# version_2.net
KiCad netlist of a schematic drawn in EAGLE
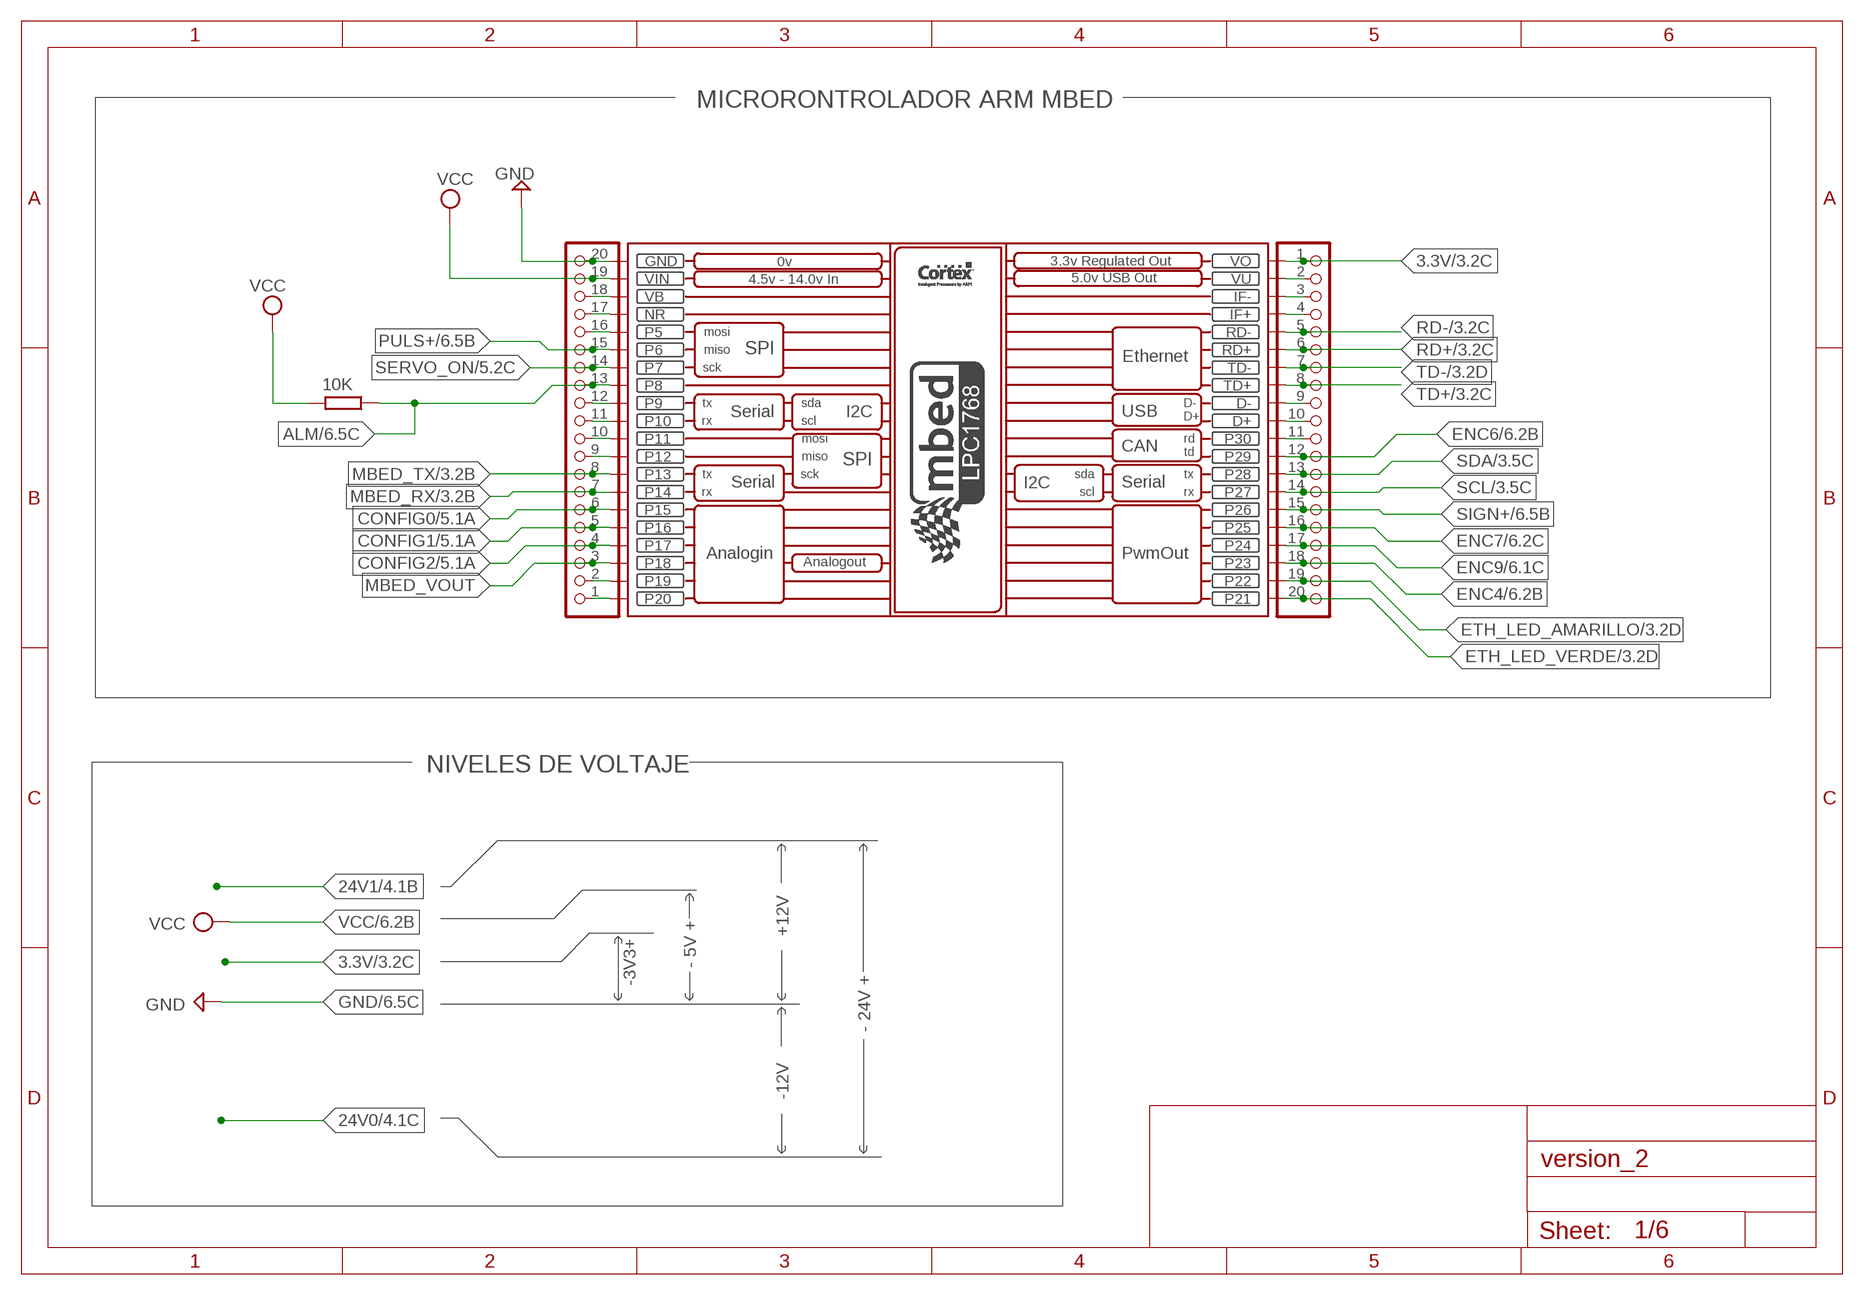
[diagram p0: schematic, sheet 1]
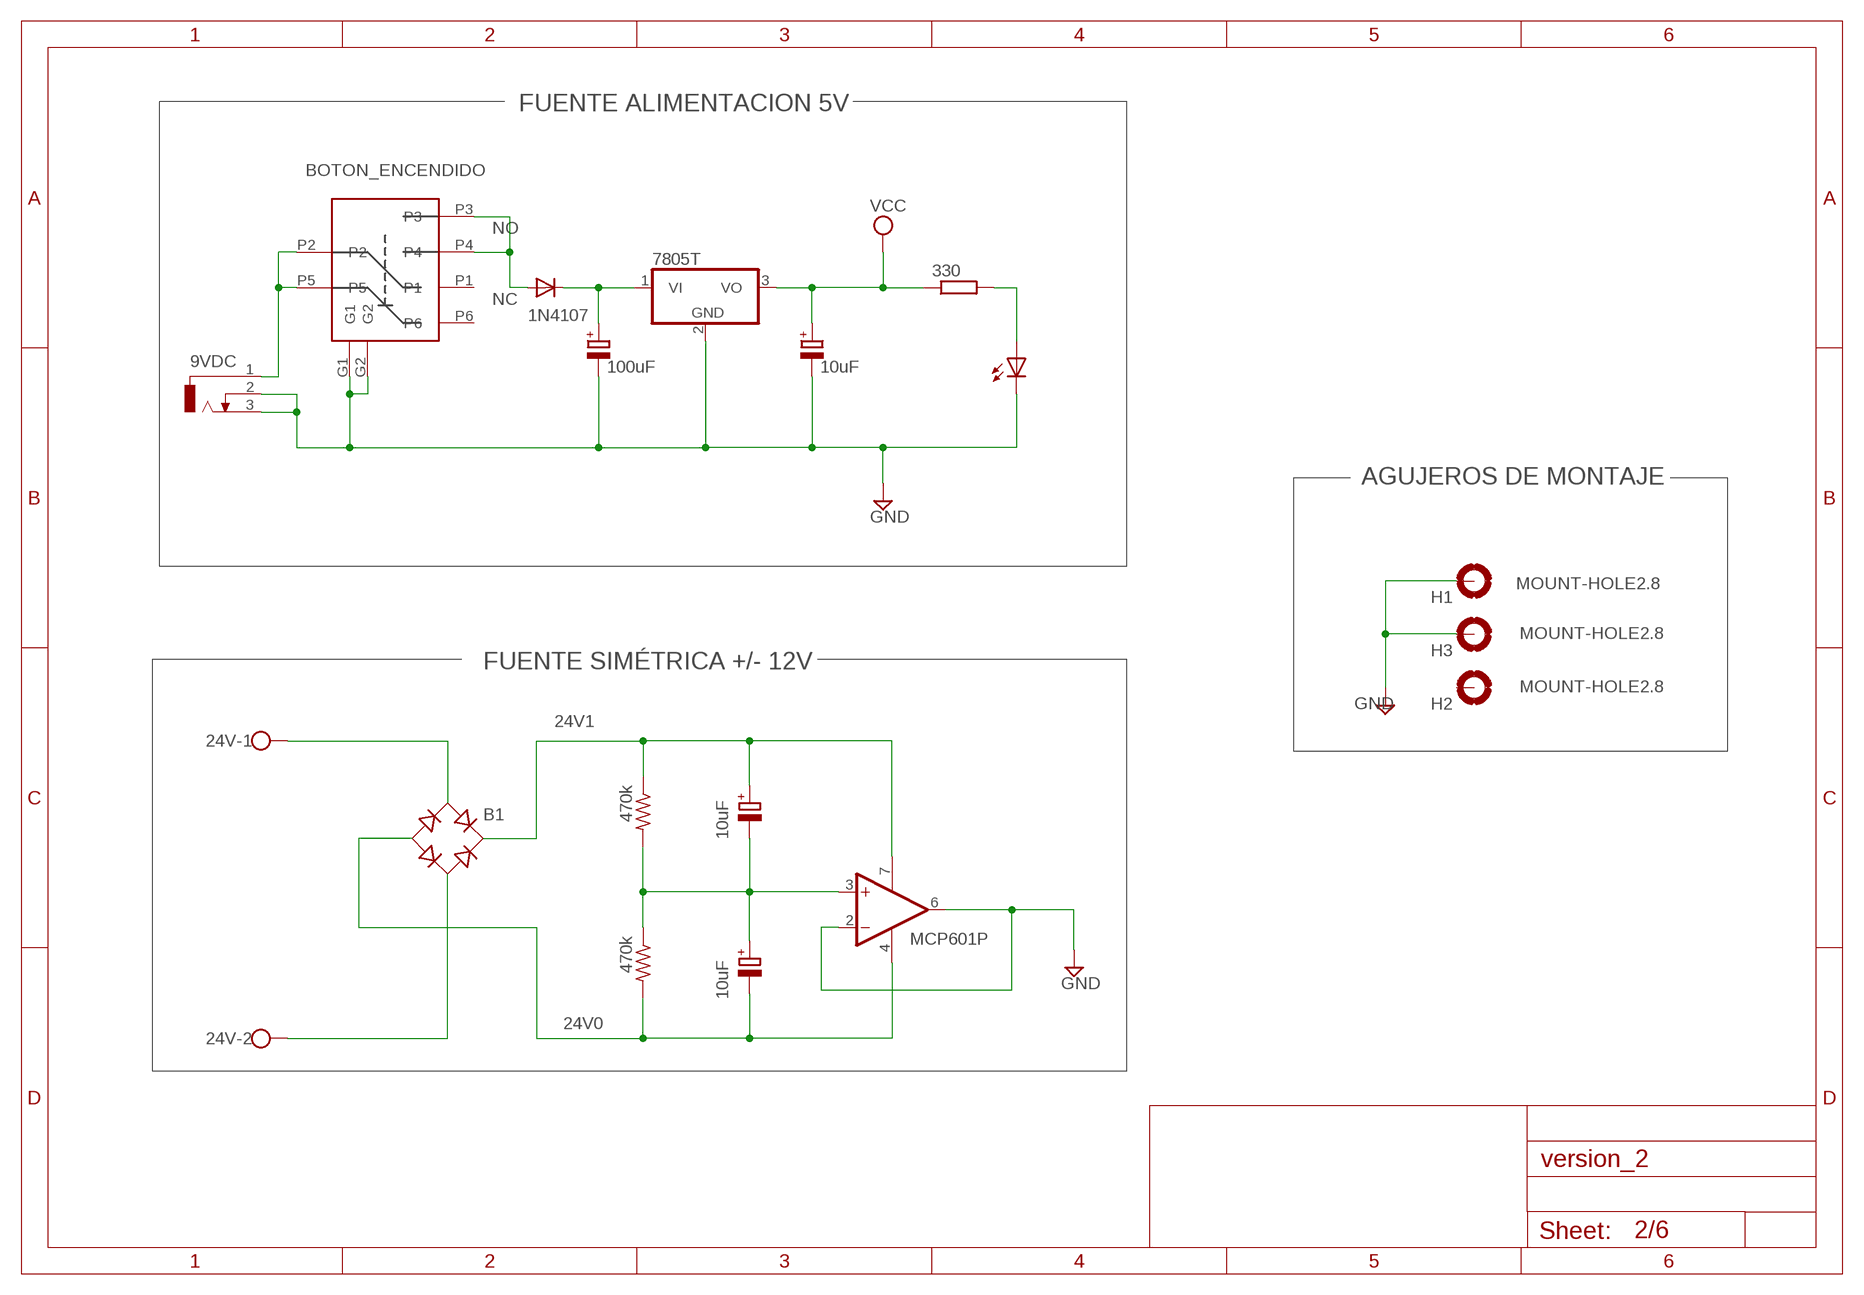
[diagram p1: schematic, sheet 2]
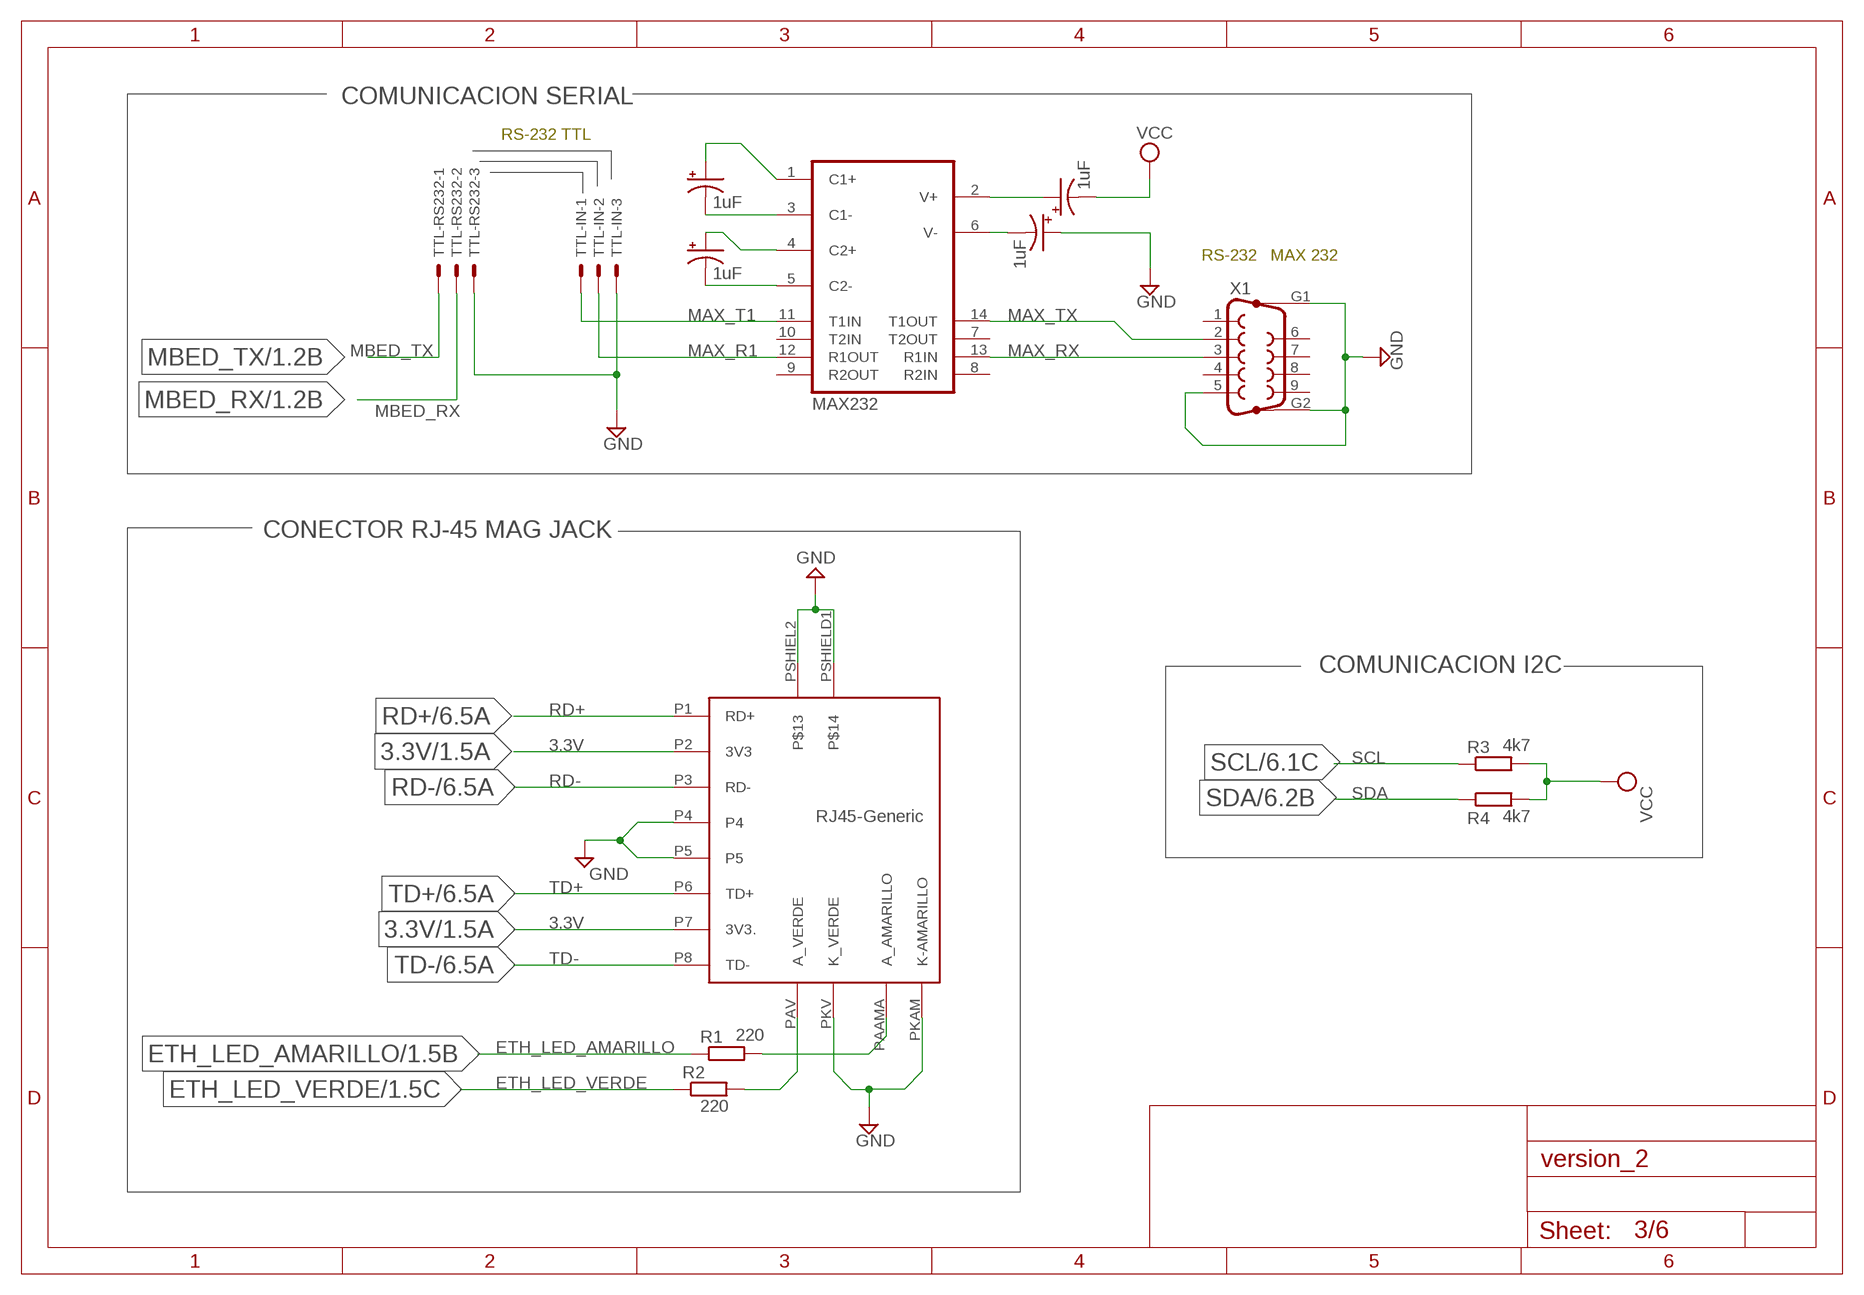
[diagram p2: schematic, sheet 3]
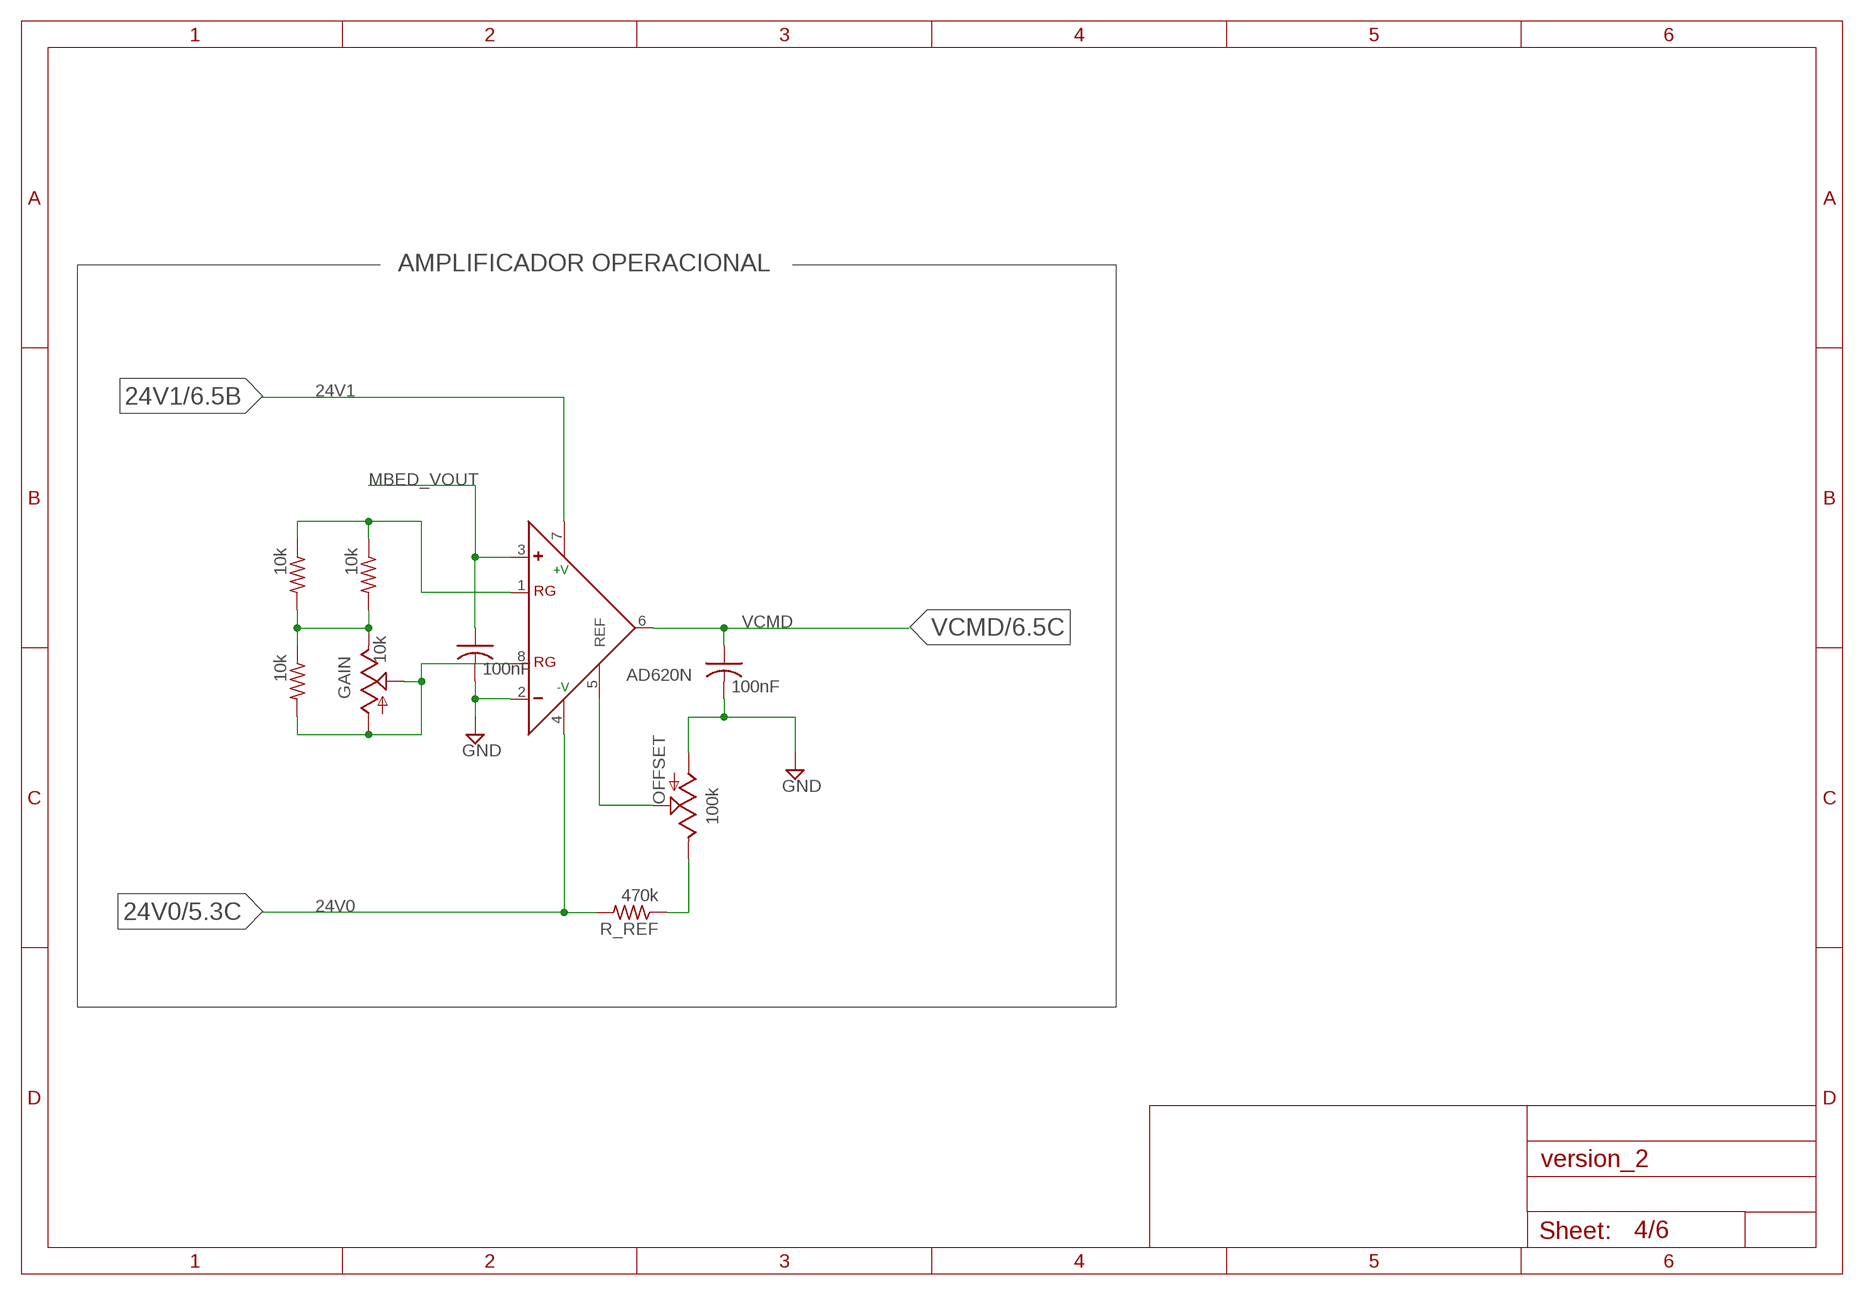
[diagram p3: schematic, sheet 4]
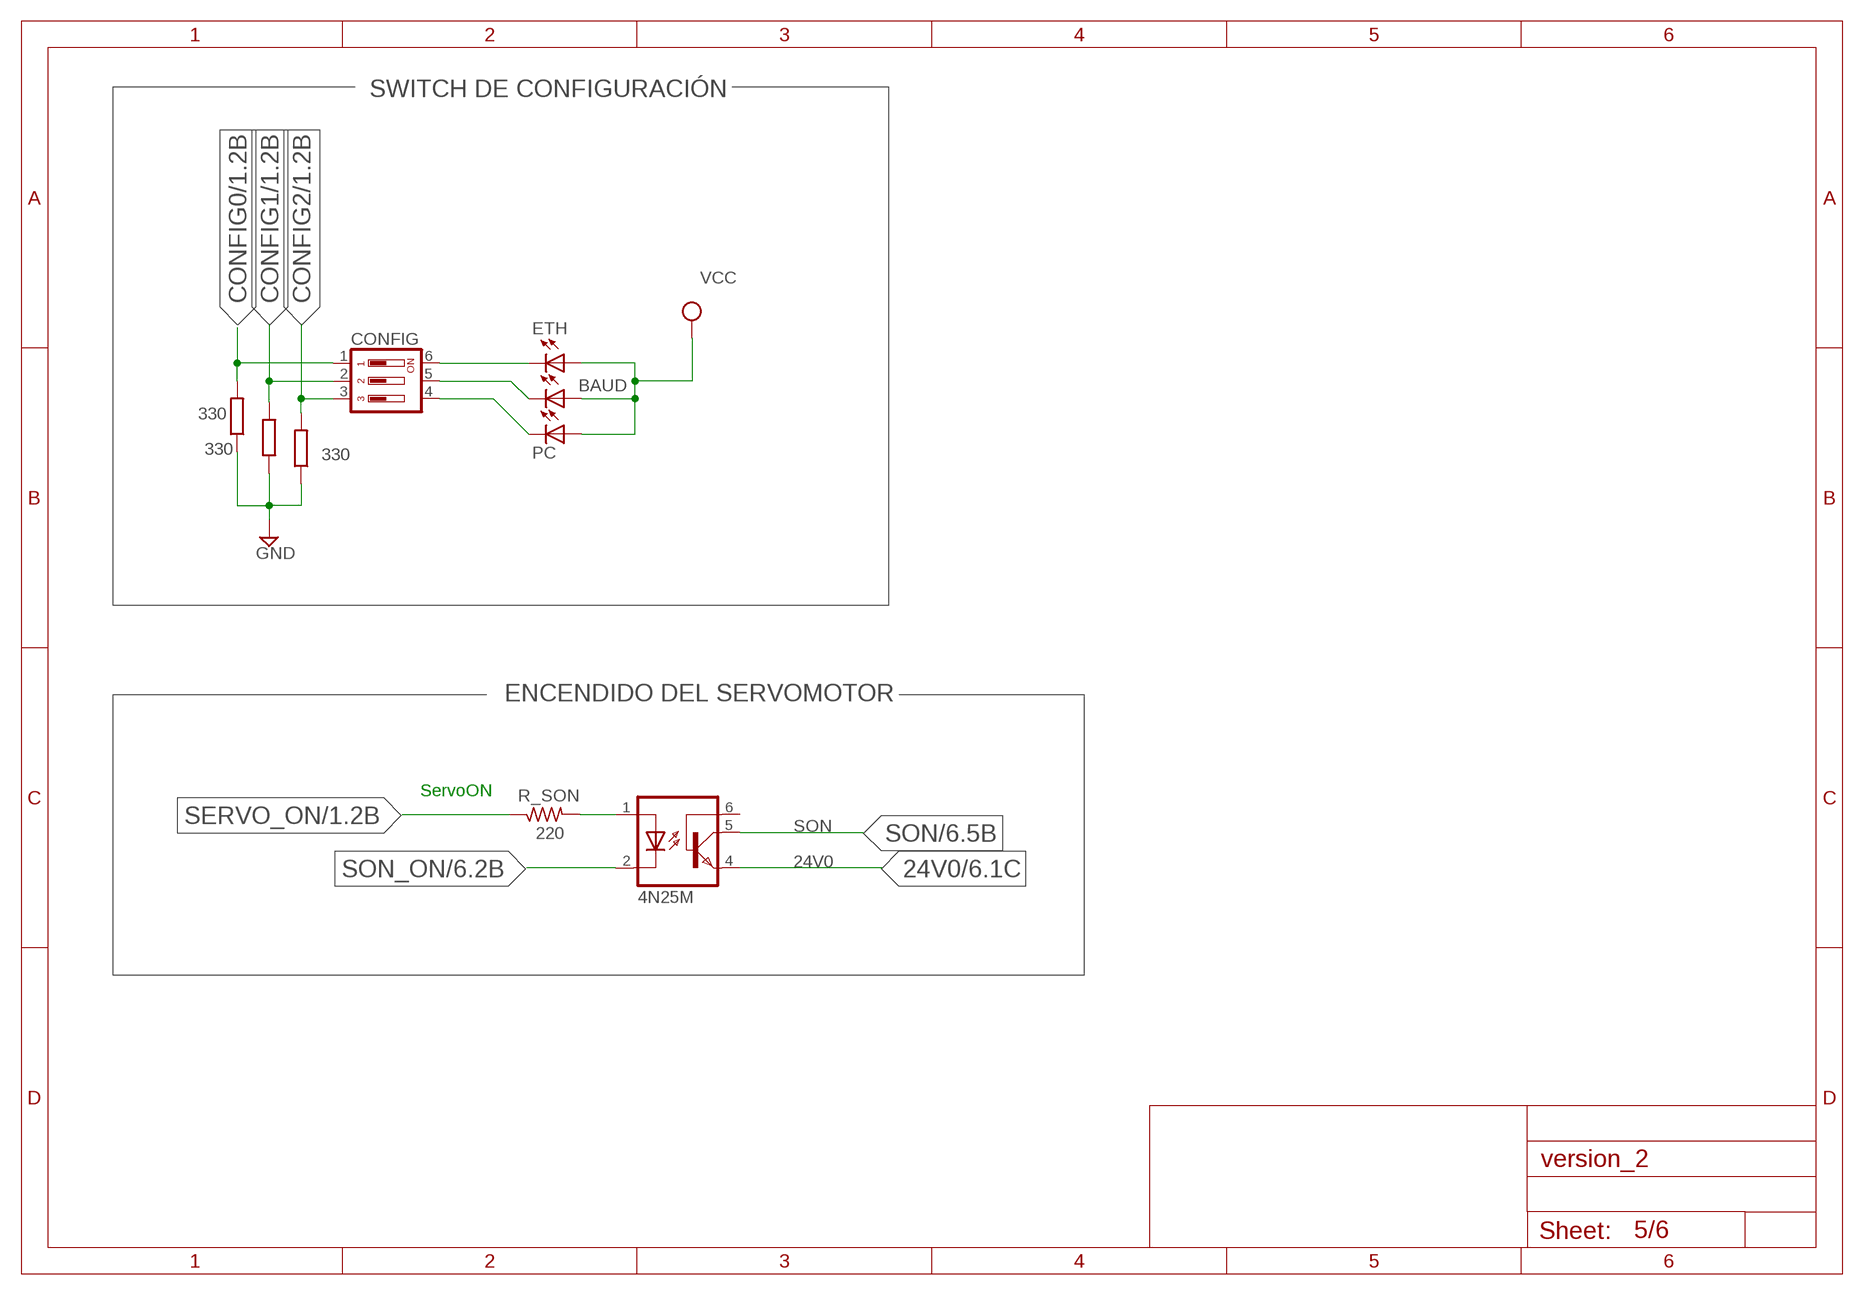
[diagram p4: schematic, sheet 5]
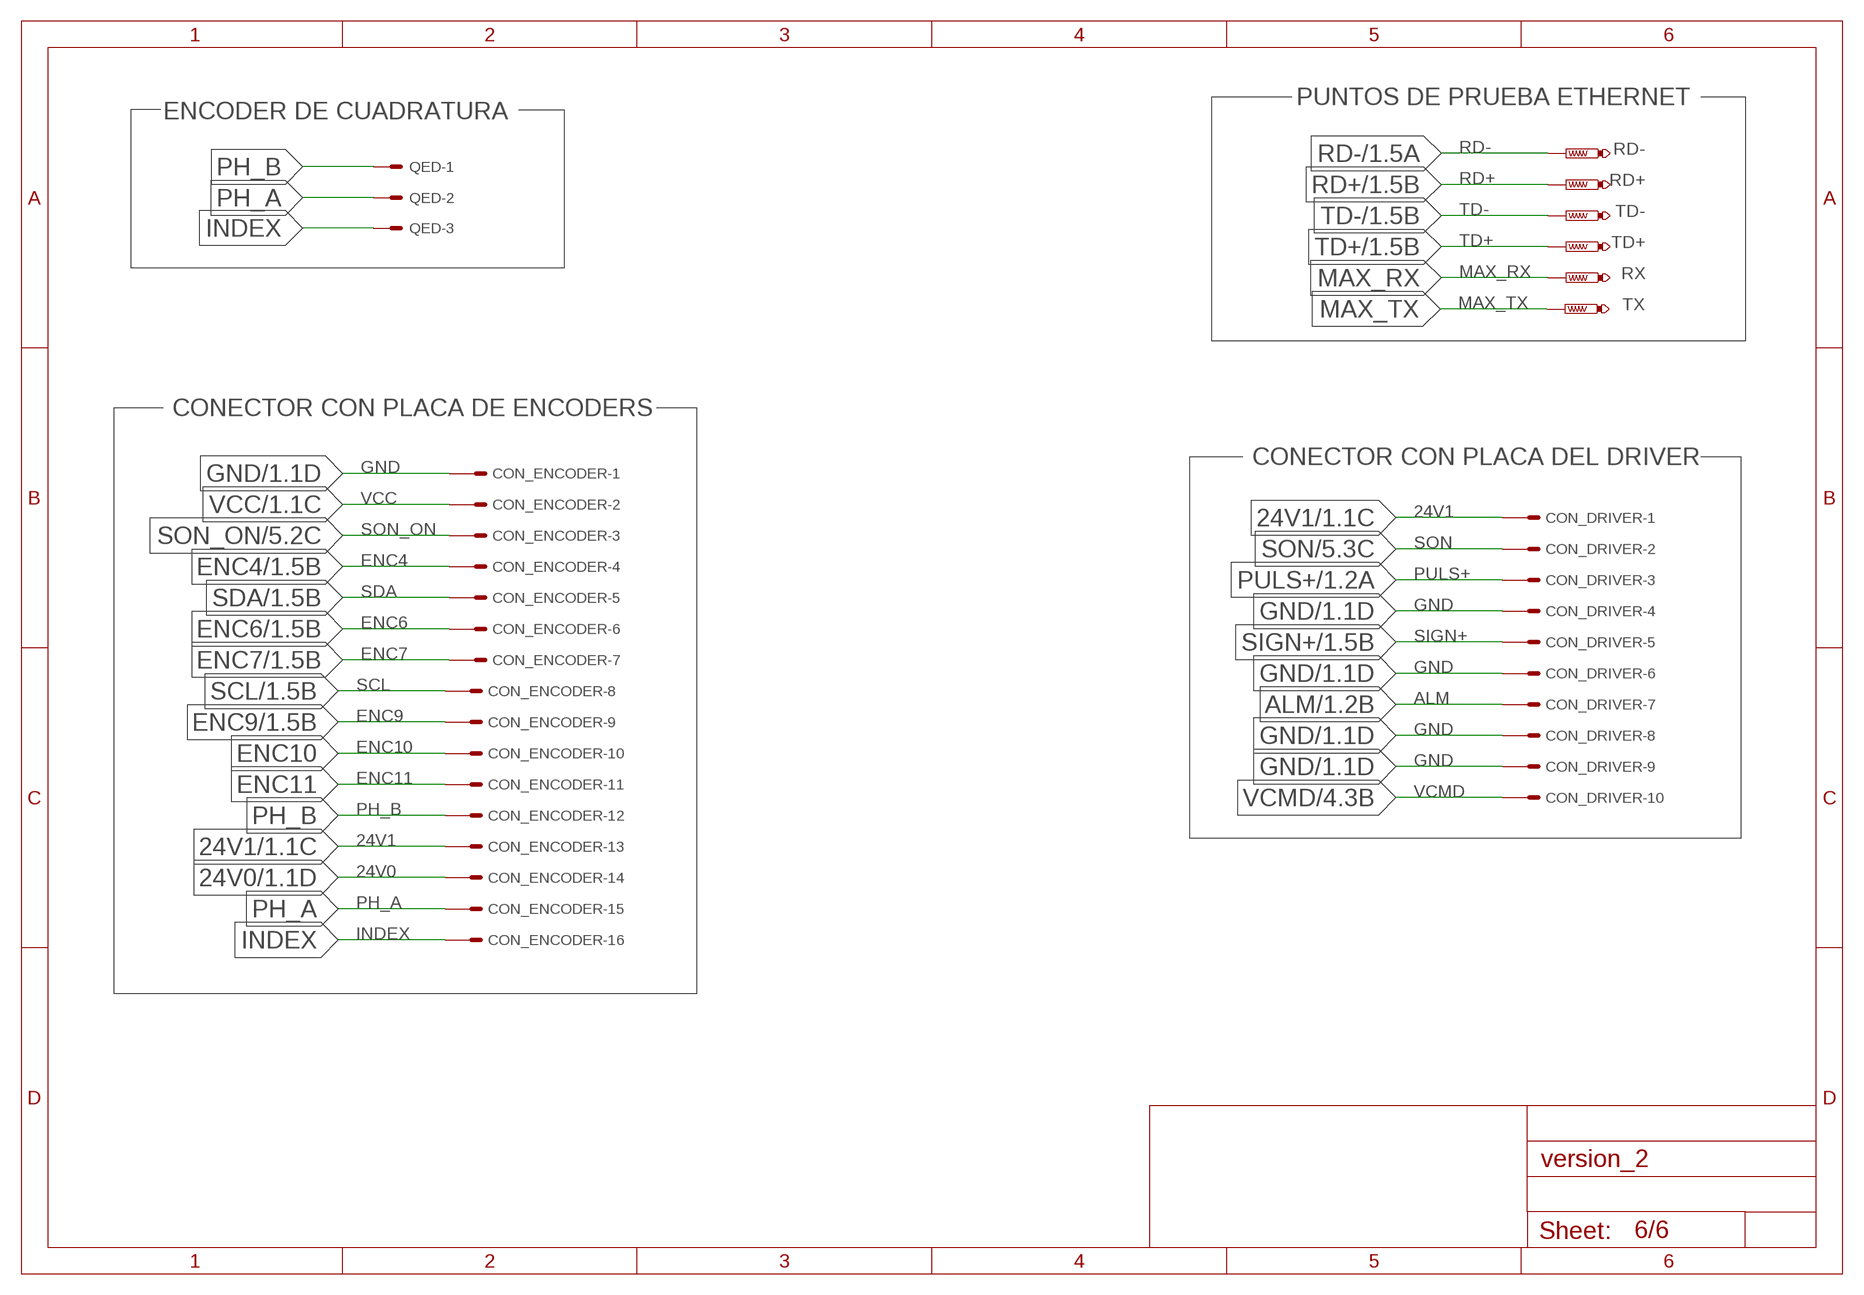
[diagram p5: schematic, sheet 6]

(export (version "E")
  (design (tool "Eeschema 10.0.6"))
  (components
    (comp (ref "CON_DRIVER")
      (value "057-010-1")
      (footprint "eagle-import:057-010-1")
      (libsource (lib "eagle-import") (part "057-010-1"))
    )
    (comp (ref "CON_ENCODER")
      (value "057-016-1")
      (footprint "eagle-import:057-016-1")
      (libsource (lib "eagle-import") (part "057-016-1"))
    )
    (comp (ref "QED")
      (value "22-23-2031")
      (footprint "eagle-import:22-23-2031")
      (fields (field (name "MF") "MOLEX"))
      (libsource (lib "eagle-import") (part "22-23-2031"))
    )
    (comp (ref "RD+")
      (value "PTR1PAD1-13Y")
      (footprint "eagle-import:P1-13Y")
      (libsource (lib "eagle-import") (part "PTR1PAD1-13Y"))
    )
    (comp (ref "RD-")
      (value "PTR1PAD1-13Y")
      (footprint "eagle-import:P1-13Y")
      (libsource (lib "eagle-import") (part "PTR1PAD1-13Y"))
    )
    (comp (ref "RX")
      (value "PTR1PAD1-13Y")
      (footprint "eagle-import:P1-13Y")
      (libsource (lib "eagle-import") (part "PTR1PAD1-13Y"))
    )
    (comp (ref "TD+")
      (value "PTR1PAD1-13Y")
      (footprint "eagle-import:P1-13Y")
      (libsource (lib "eagle-import") (part "PTR1PAD1-13Y"))
    )
    (comp (ref "TD-")
      (value "PTR1PAD1-13Y")
      (footprint "eagle-import:P1-13Y")
      (libsource (lib "eagle-import") (part "PTR1PAD1-13Y"))
    )
    (comp (ref "TX")
      (value "PTR1PAD1-13Y")
      (footprint "eagle-import:P1-13Y")
      (libsource (lib "eagle-import") (part "PTR1PAD1-13Y"))
    )
    (comp (ref "C1_MAX")
      (value "1uF")
      (footprint "eagle-import:E2,5-6E")
      (libsource (lib "eagle-import") (part "CPOL-USE2,5-6E"))
    )
    (comp (ref "C2_MAX")
      (value "1uF")
      (footprint "eagle-import:E2,5-6E")
      (libsource (lib "eagle-import") (part "CPOL-USE2,5-6E"))
    )
    (comp (ref "C3_MAX")
      (value "1uF")
      (footprint "eagle-import:E2,5-6E")
      (libsource (lib "eagle-import") (part "CPOL-USE2,5-6E"))
    )
    (comp (ref "C4_MAX")
      (value "1uF")
      (footprint "eagle-import:E2,5-6E")
      (libsource (lib "eagle-import") (part "CPOL-USE2,5-6E"))
    )
    (comp (ref "IC1")
      (value "MAX232")
      (footprint "eagle-import:DIL16")
      (libsource (lib "eagle-import") (part "MAX232"))
    )
    (comp (ref "R1")
      (value "220")
      (footprint "eagle-import:0207_15")
      (libsource (lib "eagle-import") (part "R-EU_0207/15"))
    )
    (comp (ref "R2")
      (value "220")
      (footprint "eagle-import:0207_15")
      (libsource (lib "eagle-import") (part "R-EU_0207/15"))
    )
    (comp (ref "R3")
      (value "4k7")
      (footprint "eagle-import:0204_7")
      (libsource (lib "eagle-import") (part "R-EU_0204/7"))
    )
    (comp (ref "R4")
      (value "4k7")
      (footprint "eagle-import:0204_7")
      (libsource (lib "eagle-import") (part "R-EU_0204/7"))
    )
    (comp (ref "TTL-IN")
      (value "22-23-2031")
      (footprint "eagle-import:22-23-2031")
      (fields (field (name "MF") "MOLEX"))
      (libsource (lib "eagle-import") (part "22-23-2031"))
    )
    (comp (ref "TTL-RS232")
      (value "22-23-2031")
      (footprint "eagle-import:22-23-2031")
      (fields (field (name "MF") "MOLEX"))
      (libsource (lib "eagle-import") (part "22-23-2031"))
    )
    (comp (ref "U$1")
      (value "RJ-45-GENERIC")
      (footprint "eagle-import:RJ45-GENERIC")
      (libsource (lib "eagle-import") (part "RJ-45-GENERIC"))
    )
    (comp (ref "X1")
      (value "F09HP")
      (footprint "eagle-import:F09HP")
      (libsource (lib "eagle-import") (part "F09HP"))
    )
    (comp (ref "JP_LEFT")
      (value "PINHD-1X20")
      (footprint "eagle-import:1X20")
      (libsource (lib "eagle-import") (part "PINHD-1X20"))
    )
    (comp (ref "JP_RIGHT")
      (value "PINHD-1X20")
      (footprint "eagle-import:1X20")
      (libsource (lib "eagle-import") (part "PINHD-1X20"))
    )
    (comp (ref "KIT1")
      (value "MBED_NXP_LPC1768")
      (footprint "eagle-import:MBED-KIT")
      (libsource (lib "eagle-import") (part "MBED_NXP_LPC1768"))
    )
    (comp (ref "R16_ALM")
      (value "10K")
      (footprint "eagle-import:0207_12")
      (libsource (lib "eagle-import") (part "R-EU_0207/12"))
    )
    (comp (ref "C3_AOUT")
      (value "100nF")
      (footprint "eagle-import:C025-024X044")
      (libsource (lib "eagle-import") (part "C-US025-024X044"))
    )
    (comp (ref "C5_AOUT")
      (value "100nF")
      (footprint "eagle-import:C025-024X044")
      (libsource (lib "eagle-import") (part "C-US025-024X044"))
    )
    (comp (ref "GAIN")
      (value "10k")
      (footprint "eagle-import:RJ9W")
      (libsource (lib "eagle-import") (part "TRIM_US-RJ9W"))
    )
    (comp (ref "IC4")
      (value "AD620N")
      (footprint "eagle-import:DIL08")
      (libsource (lib "eagle-import") (part "AD620N"))
    )
    (comp (ref "OFFSET")
      (value "100k")
      (footprint "eagle-import:RJ9W")
      (libsource (lib "eagle-import") (part "TRIM_US-RJ9W"))
    )
    (comp (ref "R1_G")
      (value "10k")
      (footprint "eagle-import:0204_7")
      (libsource (lib "eagle-import") (part "resistor_R-US_0204/7"))
    )
    (comp (ref "R2_G")
      (value "10k")
      (footprint "eagle-import:0204_7")
      (libsource (lib "eagle-import") (part "resistor_R-US_0204/7"))
    )
    (comp (ref "R3_G")
      (value "10k")
      (footprint "eagle-import:0204_7")
      (libsource (lib "eagle-import") (part "resistor_R-US_0204/7"))
    )
    (comp (ref "R_REF")
      (value "470k")
      (footprint "eagle-import:0204_7")
      (libsource (lib "eagle-import") (part "resistor_R-US_0204/7"))
    )
    (comp (ref "9VDC")
      (value "DCJ0303")
      (footprint "eagle-import:DCJ0303")
      (libsource (lib "eagle-import") (part "DCJ0303"))
    )
    (comp (ref "24V")
      (value "W237-02P")
      (footprint "eagle-import:W237-132")
      (libsource (lib "eagle-import") (part "W237-02P"))
    )
    (comp (ref "B1")
      (value "RB1A")
      (footprint "eagle-import:RB1A")
      (libsource (lib "eagle-import") (part "RB1A"))
    )
    (comp (ref "C1_+24")
      (value "10uF")
      (footprint "eagle-import:TT5D7")
      (libsource (lib "eagle-import") (part "CPOL-EUTT5D7"))
    )
    (comp (ref "C1_9V")
      (value "100uF")
      (footprint "eagle-import:TT5D7")
      (libsource (lib "eagle-import") (part "CPOL-EUTT5D7"))
    )
    (comp (ref "C2_0V")
      (value "10uF")
      (footprint "eagle-import:TT5D7")
      (libsource (lib "eagle-import") (part "CPOL-EUTT5D7"))
    )
    (comp (ref "C2_9V")
      (value "10uF")
      (footprint "eagle-import:TT5D7")
      (libsource (lib "eagle-import") (part "CPOL-EUTT5D7"))
    )
    (comp (ref "D1_INPUT")
      (value "1N4107")
      (footprint "eagle-import:DO35-10")
      (libsource (lib "eagle-import") (part "1N4148DO35-10"))
    )
    (comp (ref "H1")
      (value "MOUNT-HOLE2.8")
      (footprint "eagle-import:3,3-PAD")
      (libsource (lib "eagle-import") (part "MOUNT-PAD-ROUND3.3"))
    )
    (comp (ref "H2")
      (value "MOUNT-HOLE2.8")
      (footprint "eagle-import:3,3-PAD")
      (libsource (lib "eagle-import") (part "MOUNT-PAD-ROUND3.3"))
    )
    (comp (ref "H3")
      (value "MOUNT-HOLE2.8")
      (footprint "eagle-import:3,3-PAD")
      (libsource (lib "eagle-import") (part "MOUNT-PAD-ROUND3.3"))
    )
    (comp (ref "IC2")
      (value "7805T")
      (footprint "eagle-import:TO220H")
      (libsource (lib "eagle-import") (part "78T05"))
    )
    (comp (ref "IC3")
      (value "MCP601P")
      (footprint "eagle-import:DIL08")
      (libsource (lib "eagle-import") (part "MCP601P"))
    )
    (comp (ref "ON/OFF")
      (value "BOTON_ENCENDIDO")
      (footprint "eagle-import:BOTON_ENCNEDIDO")
      (libsource (lib "eagle-import") (part "BOTON_ENCENDIDO"))
    )
    (comp (ref "POWER")
      (value "LED3MM")
      (footprint "eagle-import:LED3MM")
      (libsource (lib "eagle-import") (part "LED3MM"))
    )
    (comp (ref "PWR_LED_R")
      (value "330")
      (footprint "eagle-import:0204_7")
      (libsource (lib "eagle-import") (part "R-EU_0204/7"))
    )
    (comp (ref "R1_DIV")
      (value "470k")
      (footprint "eagle-import:0207_10")
      (libsource (lib "eagle-import") (part "resistor_R-US_0207/10"))
    )
    (comp (ref "R2_DIV")
      (value "470k")
      (footprint "eagle-import:0207_10")
      (libsource (lib "eagle-import") (part "resistor_R-US_0207/10"))
    )
    (comp (ref "BAUD")
      (value "LED3MM")
      (footprint "eagle-import:LED3MM")
      (libsource (lib "eagle-import") (part "LED3MM"))
    )
    (comp (ref "CONFIG")
      (value "DIP03YL")
      (footprint "eagle-import:DIP03YL")
      (libsource (lib "eagle-import") (part "DIP03YL"))
    )
    (comp (ref "ETH")
      (value "LED3MM")
      (footprint "eagle-import:LED3MM")
      (libsource (lib "eagle-import") (part "LED3MM"))
    )
    (comp (ref "OK1")
      (value "4N25M")
      (footprint "eagle-import:DIL06")
      (libsource (lib "eagle-import") (part "4N?M25"))
    )
    (comp (ref "PC")
      (value "LED3MM")
      (footprint "eagle-import:LED3MM")
      (libsource (lib "eagle-import") (part "LED3MM"))
    )
    (comp (ref "R13")
      (value "330")
      (footprint "eagle-import:0204_7")
      (libsource (lib "eagle-import") (part "R-EU_0204/7"))
    )
    (comp (ref "R14")
      (value "330")
      (footprint "eagle-import:0204_7")
      (libsource (lib "eagle-import") (part "R-EU_0204/7"))
    )
    (comp (ref "R15")
      (value "330")
      (footprint "eagle-import:0204_7")
      (libsource (lib "eagle-import") (part "R-EU_0204/7"))
    )
    (comp (ref "R_SON")
      (value "220")
      (footprint "eagle-import:0207_7")
      (libsource (lib "eagle-import") (part "R-US_0207/7"))
    )
  )
  (nets
    (net (code "1") (name "3.3V") (class "Default")
      (node (ref "JP_RIGHT") (pin "1") (pinfunction "1_1") (pintype "passive"))
      (node (ref "KIT1") (pin "VOUT") (pinfunction "VO_VOUT") (pintype "power_in"))
      (node (ref "U$1") (pin "P2") (pinfunction "3V3_P2") (pintype "bidirectional"))
      (node (ref "U$1") (pin "P7") (pinfunction "3V3._P7") (pintype "bidirectional"))
    )
    (net (code "2") (name "24V0") (class "Default")
      (node (ref "B1") (pin "-") (pinfunction "-_-") (pintype "passive"))
      (node (ref "C2_0V") (pin "-") (pinfunction "-_-") (pintype "passive"))
      (node (ref "CON_ENCODER") (pin "14") (pinfunction "S_14") (pintype "passive"))
      (node (ref "IC3") (pin "4") (pinfunction "V-_4") (pintype "power_in"))
      (node (ref "IC4") (pin "4") (pinfunction "-V_4") (pintype "power_in"))
      (node (ref "OK1") (pin "4") (pinfunction "EMI_4") (pintype "passive"))
      (node (ref "R2_DIV") (pin "2") (pinfunction "2_2") (pintype "passive"))
      (node (ref "R_REF") (pin "2") (pinfunction "2_2") (pintype "passive"))
    )
    (net (code "3") (name "24V1") (class "Default")
      (node (ref "B1") (pin "+") (pinfunction "+_+") (pintype "passive"))
      (node (ref "C1_+24") (pin "+") (pinfunction "+_+") (pintype "passive"))
      (node (ref "CON_DRIVER") (pin "1") (pinfunction "S_1") (pintype "passive"))
      (node (ref "CON_ENCODER") (pin "13") (pinfunction "S_13") (pintype "passive"))
      (node (ref "IC3") (pin "7") (pinfunction "V+_7") (pintype "power_in"))
      (node (ref "IC4") (pin "7") (pinfunction "+V_7") (pintype "power_in"))
      (node (ref "R1_DIV") (pin "1") (pinfunction "1_1") (pintype "passive"))
    )
    (net (code "4") (name "ALM") (class "Default")
      (node (ref "CON_DRIVER") (pin "7") (pinfunction "S_7") (pintype "passive"))
      (node (ref "JP_LEFT") (pin "13") (pinfunction "13_13") (pintype "passive"))
      (node (ref "KIT1") (pin "P$8") (pinfunction "P8_P$8") (pintype "bidirectional"))
      (node (ref "R16_ALM") (pin "1") (pinfunction "1_1") (pintype "passive"))
    )
    (net (code "5") (name "CONFIG0") (class "Default")
      (node (ref "CONFIG") (pin "1") (pinfunction "1_1") (pintype "passive"))
      (node (ref "JP_LEFT") (pin "6") (pinfunction "6_6") (pintype "passive"))
      (node (ref "KIT1") (pin "P$15") (pinfunction "P15_P$15") (pintype "bidirectional"))
      (node (ref "R15") (pin "2") (pinfunction "2_2") (pintype "passive"))
    )
    (net (code "6") (name "CONFIG1") (class "Default")
      (node (ref "CONFIG") (pin "2") (pinfunction "2_2") (pintype "passive"))
      (node (ref "JP_LEFT") (pin "5") (pinfunction "5_5") (pintype "passive"))
      (node (ref "KIT1") (pin "P$16") (pinfunction "P16_P$16") (pintype "bidirectional"))
      (node (ref "R14") (pin "2") (pinfunction "2_2") (pintype "passive"))
    )
    (net (code "7") (name "CONFIG2") (class "Default")
      (node (ref "CONFIG") (pin "3") (pinfunction "3_3") (pintype "passive"))
      (node (ref "JP_LEFT") (pin "4") (pinfunction "4_4") (pintype "passive"))
      (node (ref "KIT1") (pin "P$17") (pinfunction "P17_P$17") (pintype "bidirectional"))
      (node (ref "R13") (pin "2") (pinfunction "2_2") (pintype "passive"))
    )
    (net (code "8") (name "ENC4") (class "Default")
      (node (ref "CON_ENCODER") (pin "4") (pinfunction "S_4") (pintype "passive"))
      (node (ref "JP_RIGHT") (pin "18") (pinfunction "18_18") (pintype "passive"))
      (node (ref "KIT1") (pin "P$23") (pinfunction "P23_P$23") (pintype "bidirectional"))
    )
    (net (code "9") (name "ENC6") (class "Default")
      (node (ref "CON_ENCODER") (pin "6") (pinfunction "S_6") (pintype "passive"))
      (node (ref "JP_RIGHT") (pin "12") (pinfunction "12_12") (pintype "passive"))
      (node (ref "KIT1") (pin "P$29") (pinfunction "P29_P$29") (pintype "bidirectional"))
    )
    (net (code "10") (name "ENC7") (class "Default")
      (node (ref "CON_ENCODER") (pin "7") (pinfunction "S_7") (pintype "passive"))
      (node (ref "JP_RIGHT") (pin "16") (pinfunction "16_16") (pintype "passive"))
      (node (ref "KIT1") (pin "P$25") (pinfunction "P25_P$25") (pintype "bidirectional"))
    )
    (net (code "11") (name "ENC9") (class "Default")
      (node (ref "CON_ENCODER") (pin "9") (pinfunction "S_9") (pintype "passive"))
      (node (ref "JP_RIGHT") (pin "17") (pinfunction "17_17") (pintype "passive"))
      (node (ref "KIT1") (pin "P$24") (pinfunction "P24_P$24") (pintype "bidirectional"))
    )
    (net (code "12") (name "ENC10") (class "Default")
      (node (ref "CON_ENCODER") (pin "10") (pinfunction "S_10") (pintype "passive"))
    )
    (net (code "13") (name "ENC11") (class "Default")
      (node (ref "CON_ENCODER") (pin "11") (pinfunction "S_11") (pintype "passive"))
    )
    (net (code "14") (name "ETH_LED_AMARILLO") (class "Default")
      (node (ref "JP_RIGHT") (pin "19") (pinfunction "19_19") (pintype "passive"))
      (node (ref "KIT1") (pin "P$22") (pinfunction "P22_P$22") (pintype "bidirectional"))
      (node (ref "R1") (pin "1") (pinfunction "1_1") (pintype "passive"))
    )
    (net (code "15") (name "ETH_LED_VERDE") (class "Default")
      (node (ref "JP_RIGHT") (pin "20") (pinfunction "20_20") (pintype "passive"))
      (node (ref "KIT1") (pin "P$21") (pinfunction "P21_P$21") (pintype "bidirectional"))
      (node (ref "R2") (pin "1") (pinfunction "1_1") (pintype "passive"))
    )
    (net (code "16") (name "GND") (class "Default")
      (node (ref "9VDC") (pin "2") (pinfunction "2_2") (pintype "passive"))
      (node (ref "9VDC") (pin "3") (pinfunction "3_3") (pintype "passive"))
      (node (ref "C1_9V") (pin "-") (pinfunction "-_-") (pintype "passive"))
      (node (ref "C2_9V") (pin "-") (pinfunction "-_-") (pintype "passive"))
      (node (ref "C3_AOUT") (pin "2") (pinfunction "2_2") (pintype "passive"))
      (node (ref "C3_MAX") (pin "+") (pinfunction "+_+") (pintype "passive"))
      (node (ref "C5_AOUT") (pin "2") (pinfunction "2_2") (pintype "passive"))
      (node (ref "CON_DRIVER") (pin "4") (pinfunction "S_4") (pintype "passive"))
      (node (ref "CON_DRIVER") (pin "6") (pinfunction "S_6") (pintype "passive"))
      (node (ref "CON_DRIVER") (pin "8") (pinfunction "S_8") (pintype "passive"))
      (node (ref "CON_DRIVER") (pin "9") (pinfunction "S_9") (pintype "passive"))
      (node (ref "CON_ENCODER") (pin "1") (pinfunction "S_1") (pintype "passive"))
      (node (ref "H1") (pin "B3,3") (pinfunction "MOUNT_B3,3") (pintype "passive"))
      (node (ref "H3") (pin "B3,3") (pinfunction "MOUNT_B3,3") (pintype "passive"))
      (node (ref "IC2") (pin "2") (pinfunction "GND_2") (pintype "passive"))
      (node (ref "IC3") (pin "2") (pinfunction "-IN_2") (pintype "input"))
      (node (ref "IC3") (pin "6") (pinfunction "OUT_6") (pintype "output"))
      (node (ref "IC4") (pin "2") (pinfunction "-_2") (pintype "input"))
      (node (ref "JP_LEFT") (pin "20") (pinfunction "20_20") (pintype "passive"))
      (node (ref "KIT1") (pin "GND") (pinfunction "GND_GND") (pintype "power_in"))
      (node (ref "OFFSET") (pin "A") (pinfunction "A_A") (pintype "passive"))
      (node (ref "ON/OFF") (pin "G1") (pinfunction "G1_G1") (pintype "bidirectional"))
      (node (ref "ON/OFF") (pin "G2") (pinfunction "G2_G2") (pintype "bidirectional"))
      (node (ref "POWER") (pin "K") (pinfunction "C_K") (pintype "passive"))
      (node (ref "R13") (pin "1") (pinfunction "1_1") (pintype "passive"))
      (node (ref "R14") (pin "1") (pinfunction "1_1") (pintype "passive"))
      (node (ref "R15") (pin "1") (pinfunction "1_1") (pintype "passive"))
      (node (ref "TTL-IN") (pin "3") (pinfunction "S_3") (pintype "passive"))
      (node (ref "TTL-RS232") (pin "3") (pinfunction "S_3") (pintype "passive"))
      (node (ref "U$1") (pin "P4") (pinfunction "P4_P4") (pintype "bidirectional"))
      (node (ref "U$1") (pin "P5") (pinfunction "P5_P5") (pintype "bidirectional"))
      (node (ref "U$1") (pin "PKAM") (pinfunction "K-AMARILLO_PKAM") (pintype "bidirectional"))
      (node (ref "U$1") (pin "PKV") (pinfunction "K_VERDE_PKV") (pintype "bidirectional"))
      (node (ref "U$1") (pin "PSHIEL2") (pinfunction "P$13_PSHIEL2") (pintype "bidirectional"))
      (node (ref "U$1") (pin "PSHIELD1") (pinfunction "P$14_PSHIELD1") (pintype "bidirectional"))
      (node (ref "X1") (pin "5") (pinfunction "5_5") (pintype "passive"))
      (node (ref "X1") (pin "G1") (pinfunction "G1_G1") (pintype "passive"))
      (node (ref "X1") (pin "G2") (pinfunction "G2_G2") (pintype "passive"))
    )
    (net (code "17") (name "INDEX") (class "Default")
      (node (ref "CON_ENCODER") (pin "16") (pinfunction "S_16") (pintype "passive"))
      (node (ref "QED") (pin "3") (pinfunction "S_3") (pintype "passive"))
    )
    (net (code "18") (name "MAX_R1") (class "Default")
      (node (ref "IC1") (pin "12") (pinfunction "R1OUT_12") (pintype "output"))
      (node (ref "TTL-IN") (pin "2") (pinfunction "S_2") (pintype "passive"))
    )
    (net (code "19") (name "MAX_RX") (class "Default")
      (node (ref "IC1") (pin "13") (pinfunction "R1IN_13") (pintype "input"))
      (node (ref "RX") (pin "TP") (pinfunction "TP_TP") (pintype "input"))
      (node (ref "X1") (pin "3") (pinfunction "3_3") (pintype "passive"))
    )
    (net (code "20") (name "MAX_T1") (class "Default")
      (node (ref "IC1") (pin "11") (pinfunction "T1IN_11") (pintype "input"))
      (node (ref "TTL-IN") (pin "1") (pinfunction "S_1") (pintype "passive"))
    )
    (net (code "21") (name "MAX_TX") (class "Default")
      (node (ref "IC1") (pin "14") (pinfunction "T1OUT_14") (pintype "output"))
      (node (ref "TX") (pin "TP") (pinfunction "TP_TP") (pintype "input"))
      (node (ref "X1") (pin "2") (pinfunction "2_2") (pintype "passive"))
    )
    (net (code "22") (name "MBED_RX") (class "Default")
      (node (ref "JP_LEFT") (pin "7") (pinfunction "7_7") (pintype "passive"))
      (node (ref "KIT1") (pin "P$14") (pinfunction "P14_P$14") (pintype "bidirectional"))
      (node (ref "TTL-RS232") (pin "2") (pinfunction "S_2") (pintype "passive"))
    )
    (net (code "23") (name "MBED_TX") (class "Default")
      (node (ref "JP_LEFT") (pin "8") (pinfunction "8_8") (pintype "passive"))
      (node (ref "KIT1") (pin "P$13") (pinfunction "P13_P$13") (pintype "bidirectional"))
      (node (ref "TTL-RS232") (pin "1") (pinfunction "S_1") (pintype "passive"))
    )
    (net (code "24") (name "MBED_VOUT") (class "Default")
      (node (ref "C5_AOUT") (pin "1") (pinfunction "1_1") (pintype "passive"))
      (node (ref "IC4") (pin "3") (pinfunction "+_3") (pintype "input"))
      (node (ref "JP_LEFT") (pin "3") (pinfunction "3_3") (pintype "passive"))
      (node (ref "KIT1") (pin "P$18") (pinfunction "P18_P$18") (pintype "bidirectional"))
    )
    (net (code "25") (name "Net-(9VDC-Pad1)") (class "Default")
      (node (ref "9VDC") (pin "1") (pinfunction "1_1") (pintype "passive"))
      (node (ref "ON/OFF") (pin "P2") (pinfunction "P2_P2") (pintype "bidirectional"))
      (node (ref "ON/OFF") (pin "P5") (pinfunction "P5_P5") (pintype "bidirectional"))
    )
    (net (code "26") (name "Net-(24VA-KL)") (class "Default")
      (node (ref "24V") (pin "1") (pinfunction "KL_1") (pintype "passive"))
      (node (ref "B1") (pin "AC1") (pinfunction "AC1_AC1") (pintype "passive"))
    )
    (net (code "27") (name "Net-(24VB-KL)") (class "Default")
      (node (ref "24V") (pin "2") (pinfunction "KL_2") (pintype "passive"))
      (node (ref "B1") (pin "AC2") (pinfunction "AC2_AC2") (pintype "passive"))
    )
    (net (code "28") (name "Net-(BAUD-C)") (class "Default")
      (node (ref "BAUD") (pin "K") (pinfunction "C_K") (pintype "passive"))
      (node (ref "CONFIG") (pin "5") (pinfunction "5_5") (pintype "passive"))
    )
    (net (code "29") (name "Net-(D1_INPUT-PadA)") (class "Default")
      (node (ref "D1_INPUT") (pin "A") (pinfunction "A_A") (pintype "passive"))
      (node (ref "ON/OFF") (pin "P3") (pinfunction "P3_P3") (pintype "bidirectional"))
      (node (ref "ON/OFF") (pin "P4") (pinfunction "P4_P4") (pintype "bidirectional"))
    )
    (net (code "30") (name "Net-(ETH-C)") (class "Default")
      (node (ref "CONFIG") (pin "6") (pinfunction "6_6") (pintype "passive"))
      (node (ref "ETH") (pin "K") (pinfunction "C_K") (pintype "passive"))
    )
    (net (code "31") (name "Net-(GAIN-PadA)") (class "Default")
      (node (ref "GAIN") (pin "A") (pinfunction "A_A") (pintype "passive"))
      (node (ref "GAIN") (pin "S") (pinfunction "S_S") (pintype "passive"))
      (node (ref "IC4") (pin "8") (pinfunction "RG_8") (pintype "passive"))
      (node (ref "R2_G") (pin "2") (pinfunction "2_2") (pintype "passive"))
    )
    (net (code "32") (name "Net-(GAIN-PadE)") (class "Default")
      (node (ref "GAIN") (pin "E") (pinfunction "E_E") (pintype "passive"))
      (node (ref "R1_G") (pin "2") (pinfunction "2_2") (pintype "passive"))
      (node (ref "R2_G") (pin "1") (pinfunction "1_1") (pintype "passive"))
      (node (ref "R3_G") (pin "2") (pinfunction "2_2") (pintype "passive"))
    )
    (net (code "33") (name "Net-(IC1A-C1+)") (class "Default")
      (node (ref "C1_MAX") (pin "+") (pinfunction "+_+") (pintype "passive"))
      (node (ref "IC1") (pin "1") (pinfunction "C1+_1") (pintype "bidirectional"))
    )
    (net (code "34") (name "Net-(IC1A-C1-)") (class "Default")
      (node (ref "C1_MAX") (pin "-") (pinfunction "-_-") (pintype "passive"))
      (node (ref "IC1") (pin "3") (pinfunction "C1-_3") (pintype "bidirectional"))
    )
    (net (code "35") (name "Net-(IC1A-C2+)") (class "Default")
      (node (ref "C2_MAX") (pin "+") (pinfunction "+_+") (pintype "passive"))
      (node (ref "IC1") (pin "4") (pinfunction "C2+_4") (pintype "bidirectional"))
    )
    (net (code "36") (name "Net-(IC1A-C2-)") (class "Default")
      (node (ref "C2_MAX") (pin "-") (pinfunction "-_-") (pintype "passive"))
      (node (ref "IC1") (pin "5") (pinfunction "C2-_5") (pintype "bidirectional"))
    )
    (net (code "37") (name "Net-(IC1A-V+)") (class "Default")
      (node (ref "C4_MAX") (pin "+") (pinfunction "+_+") (pintype "passive"))
      (node (ref "IC1") (pin "2") (pinfunction "V+_2") (pintype "bidirectional"))
    )
    (net (code "38") (name "Net-(IC1A-V-)") (class "Default")
      (node (ref "C3_MAX") (pin "-") (pinfunction "-_-") (pintype "passive"))
      (node (ref "IC1") (pin "6") (pinfunction "V-_6") (pintype "bidirectional"))
    )
    (net (code "39") (name "Net-(IC2-VI)") (class "Default")
      (node (ref "C1_9V") (pin "+") (pinfunction "+_+") (pintype "passive"))
      (node (ref "D1_INPUT") (pin "C") (pinfunction "C_C") (pintype "passive"))
      (node (ref "IC2") (pin "1") (pinfunction "VI_1") (pintype "input"))
    )
    (net (code "40") (name "Net-(IC3-+IN)") (class "Default")
      (node (ref "C1_+24") (pin "-") (pinfunction "-_-") (pintype "passive"))
      (node (ref "C2_0V") (pin "+") (pinfunction "+_+") (pintype "passive"))
      (node (ref "IC3") (pin "3") (pinfunction "+IN_3") (pintype "input"))
      (node (ref "R1_DIV") (pin "2") (pinfunction "2_2") (pintype "passive"))
      (node (ref "R2_DIV") (pin "1") (pinfunction "1_1") (pintype "passive"))
    )
    (net (code "41") (name "Net-(IC4-REF)") (class "Default")
      (node (ref "IC4") (pin "5") (pinfunction "REF_5") (pintype "passive"))
      (node (ref "OFFSET") (pin "S") (pinfunction "S_S") (pintype "passive"))
    )
    (net (code "42") (name "Net-(IC4-RG-Pad1)") (class "Default")
      (node (ref "IC4") (pin "1") (pinfunction "RG_1") (pintype "passive"))
      (node (ref "R1_G") (pin "1") (pinfunction "1_1") (pintype "passive"))
      (node (ref "R3_G") (pin "1") (pinfunction "1_1") (pintype "passive"))
    )
    (net (code "43") (name "Net-(JP_LEFT-Pad17)") (class "Default")
      (node (ref "JP_LEFT") (pin "17") (pinfunction "17_17") (pintype "passive"))
      (node (ref "KIT1") (pin "NR") (pinfunction "NR_NR") (pintype "power_in"))
    )
    (net (code "44") (name "Net-(JP_LEFT-Pad18)") (class "Default")
      (node (ref "JP_LEFT") (pin "18") (pinfunction "18_18") (pintype "passive"))
      (node (ref "KIT1") (pin "VB") (pinfunction "VB_VB") (pintype "power_in"))
    )
    (net (code "45") (name "Net-(JP_RIGHT-Pad2)") (class "Default")
      (node (ref "JP_RIGHT") (pin "2") (pinfunction "2_2") (pintype "passive"))
      (node (ref "KIT1") (pin "VU") (pinfunction "VU_VU") (pintype "power_in"))
    )
    (net (code "46") (name "Net-(JP_RIGHT-Pad3)") (class "Default")
      (node (ref "JP_RIGHT") (pin "3") (pinfunction "3_3") (pintype "passive"))
      (node (ref "KIT1") (pin "IF-") (pinfunction "IF-_IF-") (pintype "bidirectional"))
    )
    (net (code "47") (name "Net-(JP_RIGHT-Pad4)") (class "Default")
      (node (ref "JP_RIGHT") (pin "4") (pinfunction "4_4") (pintype "passive"))
      (node (ref "KIT1") (pin "IF+") (pinfunction "IF+_IF+") (pintype "bidirectional"))
    )
    (net (code "48") (name "Net-(JP_RIGHT-Pad9)") (class "Default")
      (node (ref "JP_RIGHT") (pin "9") (pinfunction "9_9") (pintype "passive"))
      (node (ref "KIT1") (pin "D-") (pinfunction "D-_D-") (pintype "bidirectional"))
    )
    (net (code "49") (name "Net-(JP_RIGHT-Pad10)") (class "Default")
      (node (ref "JP_RIGHT") (pin "10") (pinfunction "10_10") (pintype "passive"))
      (node (ref "KIT1") (pin "D+") (pinfunction "D+_D+") (pintype "bidirectional"))
    )
    (net (code "50") (name "Net-(KIT1-P5)") (class "Default")
      (node (ref "JP_LEFT") (pin "16") (pinfunction "16_16") (pintype "passive"))
      (node (ref "KIT1") (pin "P$5") (pinfunction "P5_P$5") (pintype "bidirectional"))
    )
    (net (code "51") (name "Net-(KIT1-P9)") (class "Default")
      (node (ref "JP_LEFT") (pin "12") (pinfunction "12_12") (pintype "passive"))
      (node (ref "KIT1") (pin "P$9") (pinfunction "P9_P$9") (pintype "bidirectional"))
    )
    (net (code "52") (name "Net-(KIT1-P10)") (class "Default")
      (node (ref "JP_LEFT") (pin "11") (pinfunction "11_11") (pintype "passive"))
      (node (ref "KIT1") (pin "P$10") (pinfunction "P10_P$10") (pintype "bidirectional"))
    )
    (net (code "53") (name "Net-(KIT1-P11)") (class "Default")
      (node (ref "JP_LEFT") (pin "10") (pinfunction "10_10") (pintype "passive"))
      (node (ref "KIT1") (pin "P$11") (pinfunction "P11_P$11") (pintype "bidirectional"))
    )
    (net (code "54") (name "Net-(KIT1-P12)") (class "Default")
      (node (ref "JP_LEFT") (pin "9") (pinfunction "9_9") (pintype "passive"))
      (node (ref "KIT1") (pin "P$12") (pinfunction "P12_P$12") (pintype "bidirectional"))
    )
    (net (code "55") (name "Net-(KIT1-P19)") (class "Default")
      (node (ref "JP_LEFT") (pin "2") (pinfunction "2_2") (pintype "passive"))
      (node (ref "KIT1") (pin "P$19") (pinfunction "P19_P$19") (pintype "bidirectional"))
    )
    (net (code "56") (name "Net-(KIT1-P20)") (class "Default")
      (node (ref "JP_LEFT") (pin "1") (pinfunction "1_1") (pintype "passive"))
      (node (ref "KIT1") (pin "P$20") (pinfunction "P20_P$20") (pintype "bidirectional"))
    )
    (net (code "57") (name "Net-(KIT1-P30)") (class "Default")
      (node (ref "JP_RIGHT") (pin "11") (pinfunction "11_11") (pintype "passive"))
      (node (ref "KIT1") (pin "P$30") (pinfunction "P30_P$30") (pintype "bidirectional"))
    )
    (net (code "58") (name "Net-(OFFSET-PadE)") (class "Default")
      (node (ref "OFFSET") (pin "E") (pinfunction "E_E") (pintype "passive"))
      (node (ref "R_REF") (pin "1") (pinfunction "1_1") (pintype "passive"))
    )
    (net (code "59") (name "Net-(OK1-A)") (class "Default")
      (node (ref "OK1") (pin "1") (pinfunction "A_1") (pintype "passive"))
      (node (ref "R_SON") (pin "2") (pinfunction "2_2") (pintype "passive"))
    )
    (net (code "60") (name "Net-(PC-C)") (class "Default")
      (node (ref "CONFIG") (pin "4") (pinfunction "4_4") (pintype "passive"))
      (node (ref "PC") (pin "K") (pinfunction "C_K") (pintype "passive"))
    )
    (net (code "61") (name "Net-(POWER-PadA)") (class "Default")
      (node (ref "POWER") (pin "A") (pinfunction "A_A") (pintype "passive"))
      (node (ref "PWR_LED_R") (pin "2") (pinfunction "2_2") (pintype "passive"))
    )
    (net (code "62") (name "Net-(U$1-A_AMARILLO)") (class "Default")
      (node (ref "R1") (pin "2") (pinfunction "2_2") (pintype "passive"))
      (node (ref "U$1") (pin "PAAMA") (pinfunction "A_AMARILLO_PAAMA") (pintype "bidirectional"))
    )
    (net (code "63") (name "Net-(U$1-A_VERDE)") (class "Default")
      (node (ref "R2") (pin "2") (pinfunction "2_2") (pintype "passive"))
      (node (ref "U$1") (pin "PAV") (pinfunction "A_VERDE_PAV") (pintype "bidirectional"))
    )
    (net (code "64") (name "PH_A") (class "Default")
      (node (ref "CON_ENCODER") (pin "15") (pinfunction "S_15") (pintype "passive"))
      (node (ref "QED") (pin "2") (pinfunction "S_2") (pintype "passive"))
    )
    (net (code "65") (name "PH_B") (class "Default")
      (node (ref "CON_ENCODER") (pin "12") (pinfunction "S_12") (pintype "passive"))
      (node (ref "QED") (pin "1") (pinfunction "S_1") (pintype "passive"))
    )
    (net (code "66") (name "PULS+") (class "Default")
      (node (ref "CON_DRIVER") (pin "3") (pinfunction "S_3") (pintype "passive"))
      (node (ref "JP_LEFT") (pin "15") (pinfunction "15_15") (pintype "passive"))
      (node (ref "KIT1") (pin "P$6") (pinfunction "P6_P$6") (pintype "bidirectional"))
    )
    (net (code "67") (name "RD+") (class "Default")
      (node (ref "JP_RIGHT") (pin "6") (pinfunction "6_6") (pintype "passive"))
      (node (ref "KIT1") (pin "RD+") (pinfunction "RD+_RD+") (pintype "bidirectional"))
      (node (ref "RD+") (pin "TP") (pinfunction "TP_TP") (pintype "input"))
      (node (ref "U$1") (pin "P1") (pinfunction "RD+_P1") (pintype "bidirectional"))
    )
    (net (code "68") (name "RD-") (class "Default")
      (node (ref "JP_RIGHT") (pin "5") (pinfunction "5_5") (pintype "passive"))
      (node (ref "KIT1") (pin "RD-") (pinfunction "RD-_RD-") (pintype "bidirectional"))
      (node (ref "RD-") (pin "TP") (pinfunction "TP_TP") (pintype "input"))
      (node (ref "U$1") (pin "P3") (pinfunction "RD-_P3") (pintype "bidirectional"))
    )
    (net (code "69") (name "SCL") (class "Default")
      (node (ref "CON_ENCODER") (pin "8") (pinfunction "S_8") (pintype "passive"))
      (node (ref "JP_RIGHT") (pin "14") (pinfunction "14_14") (pintype "passive"))
      (node (ref "KIT1") (pin "P$27") (pinfunction "P27_P$27") (pintype "bidirectional"))
      (node (ref "R3") (pin "1") (pinfunction "1_1") (pintype "passive"))
    )
    (net (code "70") (name "SDA") (class "Default")
      (node (ref "CON_ENCODER") (pin "5") (pinfunction "S_5") (pintype "passive"))
      (node (ref "JP_RIGHT") (pin "13") (pinfunction "13_13") (pintype "passive"))
      (node (ref "KIT1") (pin "P$28") (pinfunction "P28_P$28") (pintype "bidirectional"))
      (node (ref "R4") (pin "1") (pinfunction "1_1") (pintype "passive"))
    )
    (net (code "71") (name "SERVO_ON") (class "Default")
      (node (ref "JP_LEFT") (pin "14") (pinfunction "14_14") (pintype "passive"))
      (node (ref "KIT1") (pin "P$7") (pinfunction "P7_P$7") (pintype "bidirectional"))
      (node (ref "R_SON") (pin "1") (pinfunction "1_1") (pintype "passive"))
    )
    (net (code "72") (name "SIGN+") (class "Default")
      (node (ref "CON_DRIVER") (pin "5") (pinfunction "S_5") (pintype "passive"))
      (node (ref "JP_RIGHT") (pin "15") (pinfunction "15_15") (pintype "passive"))
      (node (ref "KIT1") (pin "P$26") (pinfunction "P26_P$26") (pintype "bidirectional"))
    )
    (net (code "73") (name "SON") (class "Default")
      (node (ref "CON_DRIVER") (pin "2") (pinfunction "S_2") (pintype "passive"))
      (node (ref "OK1") (pin "5") (pinfunction "COL_5") (pintype "passive"))
    )
    (net (code "74") (name "SON_ON") (class "Default")
      (node (ref "CON_ENCODER") (pin "3") (pinfunction "S_3") (pintype "passive"))
      (node (ref "OK1") (pin "2") (pinfunction "C_2") (pintype "passive"))
    )
    (net (code "75") (name "TD+") (class "Default")
      (node (ref "JP_RIGHT") (pin "8") (pinfunction "8_8") (pintype "passive"))
      (node (ref "KIT1") (pin "TD+") (pinfunction "TD+_TD+") (pintype "bidirectional"))
      (node (ref "TD+") (pin "TP") (pinfunction "TP_TP") (pintype "input"))
      (node (ref "U$1") (pin "P6") (pinfunction "TD+_P6") (pintype "bidirectional"))
    )
    (net (code "76") (name "TD-") (class "Default")
      (node (ref "JP_RIGHT") (pin "7") (pinfunction "7_7") (pintype "passive"))
      (node (ref "KIT1") (pin "TD-") (pinfunction "TD-_TD-") (pintype "bidirectional"))
      (node (ref "TD-") (pin "TP") (pinfunction "TP_TP") (pintype "input"))
      (node (ref "U$1") (pin "P8") (pinfunction "TD-_P8") (pintype "bidirectional"))
    )
    (net (code "77") (name "VCC") (class "Default")
      (node (ref "BAUD") (pin "A") (pinfunction "A_A") (pintype "passive"))
      (node (ref "C2_9V") (pin "+") (pinfunction "+_+") (pintype "passive"))
      (node (ref "C4_MAX") (pin "-") (pinfunction "-_-") (pintype "passive"))
      (node (ref "CON_ENCODER") (pin "2") (pinfunction "S_2") (pintype "passive"))
      (node (ref "ETH") (pin "A") (pinfunction "A_A") (pintype "passive"))
      (node (ref "IC2") (pin "3") (pinfunction "VO_3") (pintype "passive"))
      (node (ref "JP_LEFT") (pin "19") (pinfunction "19_19") (pintype "passive"))
      (node (ref "KIT1") (pin "VIN") (pinfunction "VIN_VIN") (pintype "power_in"))
      (node (ref "PC") (pin "A") (pinfunction "A_A") (pintype "passive"))
      (node (ref "PWR_LED_R") (pin "1") (pinfunction "1_1") (pintype "passive"))
      (node (ref "R16_ALM") (pin "2") (pinfunction "2_2") (pintype "passive"))
      (node (ref "R3") (pin "2") (pinfunction "2_2") (pintype "passive"))
      (node (ref "R4") (pin "2") (pinfunction "2_2") (pintype "passive"))
    )
    (net (code "78") (name "VCMD") (class "Default")
      (node (ref "C3_AOUT") (pin "1") (pinfunction "1_1") (pintype "passive"))
      (node (ref "CON_DRIVER") (pin "10") (pinfunction "S_10") (pintype "passive"))
      (node (ref "IC4") (pin "6") (pinfunction "OUT_6") (pintype "output"))
    )
    (net (code "79") (name "unconnected-(H2-MOUNT-PadB3,3)") (class "Default")
      (node (ref "H2") (pin "B3,3") (pinfunction "MOUNT_B3,3") (pintype "passive"))
    )
    (net (code "80") (name "unconnected-(IC1A-R2IN-Pad8)") (class "Default")
      (node (ref "IC1") (pin "8") (pinfunction "R2IN_8") (pintype "input"))
    )
    (net (code "81") (name "unconnected-(IC1A-R2OUT-Pad9)") (class "Default")
      (node (ref "IC1") (pin "9") (pinfunction "R2OUT_9") (pintype "output"))
    )
    (net (code "82") (name "unconnected-(IC1A-T2IN-Pad10)") (class "Default")
      (node (ref "IC1") (pin "10") (pinfunction "T2IN_10") (pintype "input"))
    )
    (net (code "83") (name "unconnected-(IC1A-T2OUT-Pad7)") (class "Default")
      (node (ref "IC1") (pin "7") (pinfunction "T2OUT_7") (pintype "output"))
    )
    (net (code "84") (name "unconnected-(OK1-BAS-Pad6)") (class "Default")
      (node (ref "OK1") (pin "6") (pinfunction "BAS_6") (pintype "passive"))
    )
    (net (code "85") (name "unconnected-(ON/OFF-PadP1)") (class "Default")
      (node (ref "ON/OFF") (pin "P1") (pinfunction "P1_P1") (pintype "bidirectional"))
    )
    (net (code "86") (name "unconnected-(ON/OFF-PadP6)") (class "Default")
      (node (ref "ON/OFF") (pin "P6") (pinfunction "P6_P6") (pintype "bidirectional"))
    )
    (net (code "87") (name "unconnected-(X1-Pad1)") (class "Default")
      (node (ref "X1") (pin "1") (pinfunction "1_1") (pintype "passive"))
    )
    (net (code "88") (name "unconnected-(X1-Pad4)") (class "Default")
      (node (ref "X1") (pin "4") (pinfunction "4_4") (pintype "passive"))
    )
    (net (code "89") (name "unconnected-(X1-Pad6)") (class "Default")
      (node (ref "X1") (pin "6") (pinfunction "6_6") (pintype "passive"))
    )
    (net (code "90") (name "unconnected-(X1-Pad7)") (class "Default")
      (node (ref "X1") (pin "7") (pinfunction "7_7") (pintype "passive"))
    )
    (net (code "91") (name "unconnected-(X1-Pad8)") (class "Default")
      (node (ref "X1") (pin "8") (pinfunction "8_8") (pintype "passive"))
    )
    (net (code "92") (name "unconnected-(X1-Pad9)") (class "Default")
      (node (ref "X1") (pin "9") (pinfunction "9_9") (pintype "passive"))
    )
  )
)
